# Receiver.net
KiCad netlist of a schematic drawn in EAGLE
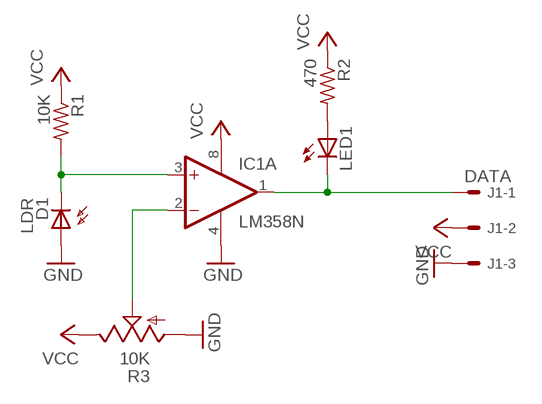
[diagram p0: schematic, sheet 1]

(export (version "E")
  (design (tool "Eeschema 10.0.6"))
  (components
    (comp (ref "D1")
      (value "LDR")
      (footprint "eagle-import:LED3MM")
      (libsource (lib "eagle-import") (part "PHOTODIODE"))
    )
    (comp (ref "IC1")
      (value "LM358N")
      (footprint "eagle-import:DIL08")
      (libsource (lib "eagle-import") (part "LM358N"))
    )
    (comp (ref "J1")
      (value "DATA")
      (footprint "eagle-import:7395-03")
      (libsource (lib "eagle-import") (part "CON_MOLEX-?-0305-7038"))
    )
    (comp (ref "LED1")
      (value "LED3MM")
      (footprint "eagle-import:LED3MM")
      (libsource (lib "eagle-import") (part "LED3MM"))
    )
    (comp (ref "R1")
      (value "10K")
      (footprint "eagle-import:0204_7")
      (libsource (lib "eagle-import") (part "RESISTOR0204/7"))
    )
    (comp (ref "R2")
      (value "470")
      (footprint "eagle-import:0204_7")
      (libsource (lib "eagle-import") (part "RESISTOR0204/7"))
    )
    (comp (ref "R3")
      (value "10K")
      (footprint "eagle-import:CA6V")
      (libsource (lib "eagle-import") (part "TRIMPOTCA6V"))
    )
  )
  (nets
    (net (code "1") (name "GND") (class "Default")
      (node (ref "D1") (pin "A") (pinfunction "A_A") (pintype "passive"))
      (node (ref "IC1") (pin "4") (pinfunction "V-_4") (pintype "power_in"))
      (node (ref "J1") (pin "3") (pinfunction "S_3") (pintype "passive"))
      (node (ref "R3") (pin "A") (pinfunction "A_A") (pintype "passive"))
    )
    (net (code "2") (name "Net-(D1-C)") (class "Default")
      (node (ref "D1") (pin "K") (pinfunction "C_K") (pintype "passive"))
      (node (ref "IC1") (pin "3") (pinfunction "+IN_3") (pintype "input"))
      (node (ref "R1") (pin "2") (pinfunction "2_2") (pintype "passive"))
    )
    (net (code "3") (name "Net-(IC1A--IN)") (class "Default")
      (node (ref "IC1") (pin "2") (pinfunction "-IN_2") (pintype "input"))
      (node (ref "R3") (pin "S") (pinfunction "S_S") (pintype "passive"))
    )
    (net (code "4") (name "Net-(IC1A-OUT)") (class "Default")
      (node (ref "IC1") (pin "1") (pinfunction "OUT_1") (pintype "output"))
      (node (ref "J1") (pin "1") (pinfunction "S_1") (pintype "passive"))
      (node (ref "LED1") (pin "K") (pinfunction "C_K") (pintype "passive"))
    )
    (net (code "5") (name "Net-(LED1-PadA)") (class "Default")
      (node (ref "LED1") (pin "A") (pinfunction "A_A") (pintype "passive"))
      (node (ref "R2") (pin "2") (pinfunction "2_2") (pintype "passive"))
    )
    (net (code "6") (name "VCC") (class "Default")
      (node (ref "IC1") (pin "8") (pinfunction "V+_8") (pintype "power_in"))
      (node (ref "J1") (pin "2") (pinfunction "S_2") (pintype "passive"))
      (node (ref "R1") (pin "1") (pinfunction "1_1") (pintype "passive"))
      (node (ref "R2") (pin "1") (pinfunction "1_1") (pintype "passive"))
      (node (ref "R3") (pin "E") (pinfunction "E_E") (pintype "passive"))
    )
  )
)
